# pm25-bme680.net
KiCad netlist of a schematic drawn in EAGLE
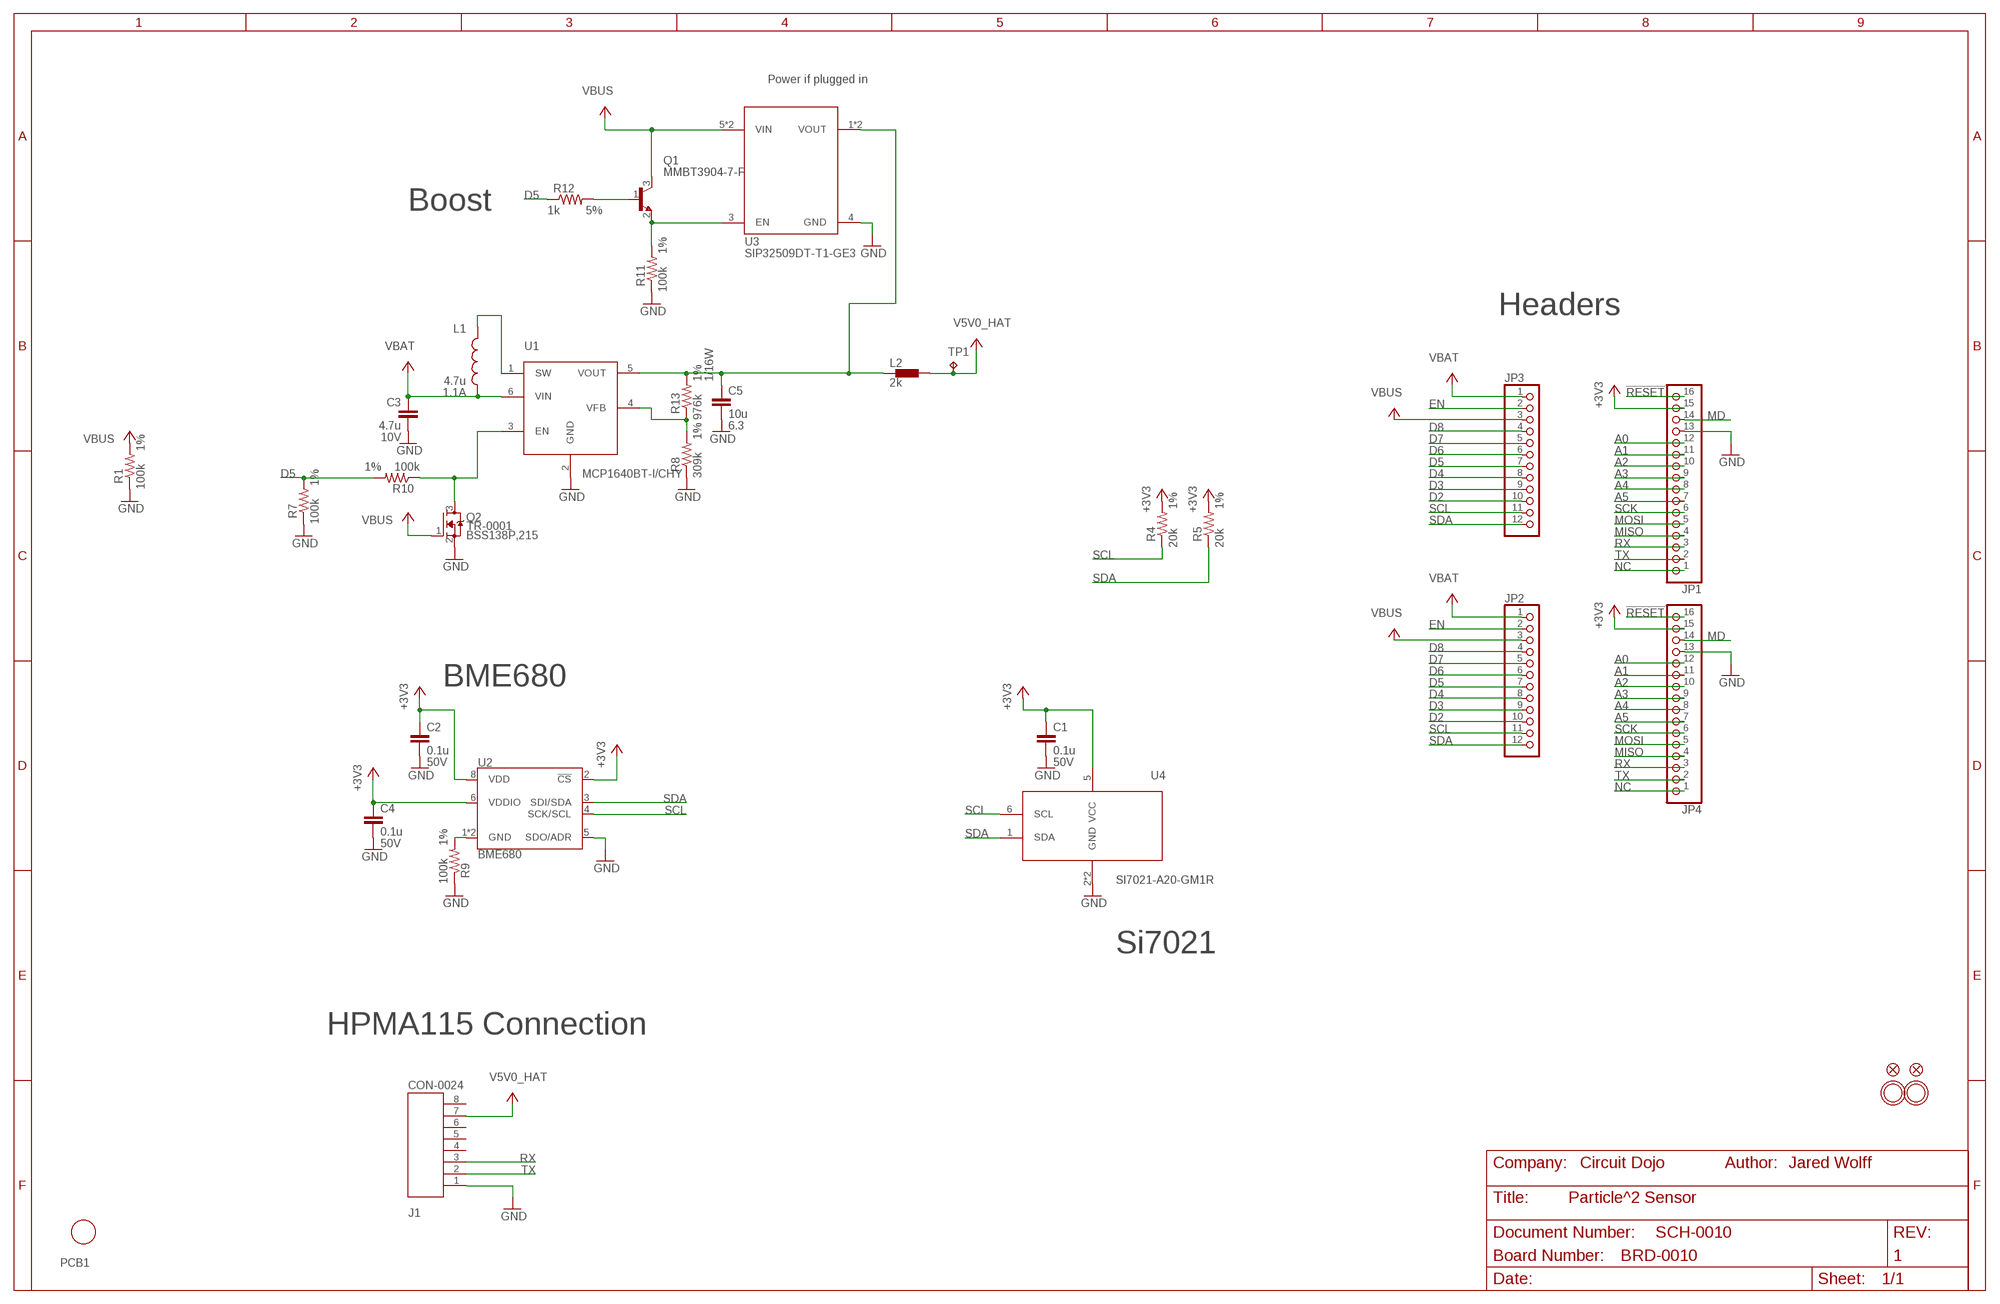
[diagram p0: schematic, sheet 1]

(export (version "E")
  (design (tool "Eeschema 10.0.6"))
  (components
    (comp (ref "C1")
      (value "0.1u")
      (footprint "eagle-import:CAPC1005X55N")
      (fields
        (field (name "VOLTHIGH") "50V")
        (field (name "MF") "Taiyo Yuden")
        (field (name "MPN") "UMK105BJ104KV-F")
      )
      (libsource (lib "eagle-import") (part "CAP-0017"))
    )
    (comp (ref "C2")
      (value "0.1u")
      (footprint "eagle-import:CAPC1005X55N")
      (fields
        (field (name "VOLTHIGH") "50V")
        (field (name "MF") "Taiyo Yuden")
        (field (name "MPN") "UMK105BJ104KV-F")
      )
      (libsource (lib "eagle-import") (part "CAP-0017"))
    )
    (comp (ref "C3")
      (value "4.7u")
      (footprint "eagle-import:C0603")
      (fields (field (name "VOLTHIGH") "10V") (field (name "MPN") "CL10A475MP5LNNC"))
      (libsource (lib "eagle-import") (part "CAP-0010"))
    )
    (comp (ref "C4")
      (value "0.1u")
      (footprint "eagle-import:CAPC1005X55N")
      (fields
        (field (name "VOLTHIGH") "50V")
        (field (name "MF") "Taiyo Yuden")
        (field (name "MPN") "UMK105BJ104KV-F")
      )
      (libsource (lib "eagle-import") (part "CAP-0017"))
    )
    (comp (ref "C5")
      (value "10u")
      (footprint "eagle-import:C0603")
      (fields (field (name "MPN") "JMK107ABJ106MA-T") (field (name "VOLTHIGH") "6.3"))
      (libsource (lib "eagle-import") (part "CAP-0603-10U-6.3V"))
    )
    (comp (ref "J1")
      (value "CON-0024")
      (footprint "eagle-import:0532610871")
      (fields (field (name "MPN") "0532610871"))
      (libsource (lib "eagle-import") (part "CON-0024"))
    )
    (comp (ref "JP1")
      (value "HEADER-1X16ROUND")
      (footprint "eagle-import:1X16_ROUND")
      (fields (field (name "MPN") "PPPC161LFBN-RC"))
      (libsource (lib "eagle-import") (part "HEADER-1X16ROUND"))
    )
    (comp (ref "JP2")
      (value "HEADER-1X12")
      (footprint "eagle-import:1X12_ROUND")
      (libsource (lib "eagle-import") (part "HEADER-1X12"))
    )
    (comp (ref "JP3")
      (value "HEADER-1X12")
      (footprint "eagle-import:1X12_ROUND")
      (fields (field (name "MPN") "PPPC121LFBN-RC"))
      (libsource (lib "eagle-import") (part "HEADER-1X12"))
    )
    (comp (ref "JP4")
      (value "HEADER-1X16ROUND")
      (footprint "eagle-import:1X16_ROUND")
      (libsource (lib "eagle-import") (part "HEADER-1X16ROUND"))
    )
    (comp (ref "L1")
      (value "4.7u")
      (footprint "eagle-import:IND-2P0X2P0X1P2")
      (fields (field (name "CURRENT") "1.1A") (field (name "MPN") "NRV2012T4R7MGF"))
      (libsource (lib "eagle-import") (part "IND-0003"))
    )
    (comp (ref "L2")
      (value "2k")
      (footprint "eagle-import:R0805")
      (fields (field (name "MPN") "CIM21J202NE"))
      (libsource (lib "eagle-import") (part "FERRITE-0805"))
    )
    (comp (ref "PCB1")
      (value "PCB-BME680-SI7021")
      (footprint "eagle-import:PLACEHOLDER")
      (fields (field (name "MPN") "BRD-0011"))
      (libsource (lib "eagle-import") (part "PCB-BME680-SI7021"))
    )
    (comp (ref "Q1")
      (value "TRANSISTOR-NPN-40V-0.2A-SOT23")
      (footprint "eagle-import:SOT23")
      (fields (field (name "MPN") "MMBT3904-7-F"))
      (libsource (lib "eagle-import") (part "TRANSISTOR-SOT23-NPN-40V-0.2A"))
    )
    (comp (ref "Q2")
      (value "TR-0001")
      (footprint "eagle-import:SOT23")
      (fields (field (name "MPN") "BSS138P,215"))
      (libsource (lib "eagle-import") (part "TR-0001"))
    )
    (comp (ref "R1")
      (value "100k")
      (footprint "eagle-import:R0402")
      (fields (field (name "TOLERANCE") "1%") (field (name "MPN") "RC0402FR07100KL"))
      (libsource (lib "eagle-import") (part "RES-0041"))
    )
    (comp (ref "R4")
      (value "20k")
      (footprint "eagle-import:R0402")
      (fields (field (name "TOLERANCE") "1%") (field (name "MPN") "RC0402FR-0720KL"))
      (libsource (lib "eagle-import") (part "RES-0054"))
    )
    (comp (ref "R5")
      (value "20k")
      (footprint "eagle-import:R0402")
      (fields (field (name "TOLERANCE") "1%") (field (name "MPN") "RC0402FR-0720KL"))
      (libsource (lib "eagle-import") (part "RES-0054"))
    )
    (comp (ref "R7")
      (value "100k")
      (footprint "eagle-import:R0402")
      (fields (field (name "TOLERANCE") "1%") (field (name "MPN") "RC0402FR07100KL"))
      (libsource (lib "eagle-import") (part "RES-0041"))
    )
    (comp (ref "R8")
      (value "309k")
      (footprint "eagle-import:R0402")
      (fields
        (field (name "MPN") "RC0402FR-07309KL")
        (field (name "POWER") "1/16W")
        (field (name "TOLERANCE") "1%")
      )
      (libsource (lib "eagle-import") (part "RES-0402-309K-1%"))
    )
    (comp (ref "R9")
      (value "100k")
      (footprint "eagle-import:R0402")
      (fields (field (name "TOLERANCE") "1%") (field (name "MPN") "RC0402FR07100KL"))
      (libsource (lib "eagle-import") (part "RES-0041"))
    )
    (comp (ref "R10")
      (value "100k")
      (footprint "eagle-import:R0402")
      (fields (field (name "TOLERANCE") "1%") (field (name "MPN") "RC0402FR07100KL"))
      (libsource (lib "eagle-import") (part "RES-0041"))
    )
    (comp (ref "R11")
      (value "100k")
      (footprint "eagle-import:R0402")
      (fields (field (name "TOLERANCE") "1%") (field (name "MPN") "RC0402FR07100KL"))
      (libsource (lib "eagle-import") (part "RES-0041"))
    )
    (comp (ref "R12")
      (value "1k")
      (footprint "eagle-import:R0402")
      (fields (field (name "TOLERANCE") "5%") (field (name "MPN") "RC0402JR-071KL"))
      (libsource (lib "eagle-import") (part "RES-0039"))
    )
    (comp (ref "R13")
      (value "976k")
      (footprint "eagle-import:R0402")
      (fields
        (field (name "MPN") "RC0402FR-07976KL")
        (field (name "POWER") "1/16W")
        (field (name "TOLERANCE") "1%")
      )
      (libsource (lib "eagle-import") (part "RES-0402-976K-1%"))
    )
    (comp (ref "TP1")
      (value "TP")
      (footprint "eagle-import:TP-1P27")
      (libsource (lib "eagle-import") (part "TP"))
    )
    (comp (ref "U$31")
      (value "MOUNTINGHOLE2.5")
      (footprint "eagle-import:MOUNTINGHOLE_2.5_PLATED")
      (libsource (lib "eagle-import") (part "MOUNTINGHOLE2.5"))
    )
    (comp (ref "U$32")
      (value "MOUNTINGHOLE2.5")
      (footprint "eagle-import:MOUNTINGHOLE_2.5_PLATED")
      (libsource (lib "eagle-import") (part "MOUNTINGHOLE2.5"))
    )
    (comp (ref "U$34")
      (value "FIDUCIAL\"\"")
      (footprint "eagle-import:FIDUCIAL_1MM")
      (libsource (lib "eagle-import") (part "FIDUCIAL{dblquote}{dblquote}"))
    )
    (comp (ref "U$35")
      (value "FIDUCIAL\"\"")
      (footprint "eagle-import:FIDUCIAL_1MM")
      (libsource (lib "eagle-import") (part "FIDUCIAL{dblquote}{dblquote}"))
    )
    (comp (ref "U1")
      (value "POWER-VREG-FB-EN-SW-350MA")
      (footprint "eagle-import:SOT23-6")
      (fields (field (name "MPN") "MCP1640BT-I/CHY"))
      (libsource (lib "eagle-import") (part "POWER-VREG-FB-EN-SW-350MA"))
    )
    (comp (ref "U2")
      (value "BME680")
      (footprint "eagle-import:LGA3.0X3.0")
      (fields (field (name "MF") "Bosch Sensortec"))
      (libsource (lib "eagle-import") (part "BME680"))
    )
    (comp (ref "U3")
      (value "POWER-SWITCH-SIP32509DT")
      (footprint "eagle-import:SOT23-6")
      (fields (field (name "MPN") "SIP32509DT-T1-GE3"))
      (libsource (lib "eagle-import") (part "POWER-SWITCH-SIP32509DT"))
    )
    (comp (ref "U4")
      (value "SI7021-A20-GM1R")
      (footprint "eagle-import:SON100P300X300X80-7N")
      (fields (field (name "MPN") "SI7021-A20-GM1R"))
      (libsource (lib "eagle-import") (part "SI7021-A20-GM1R"))
    )
  )
  (nets
    (net (code "1") (name "+3V3") (class "Default")
      (node (ref "C1") (pin "1") (pinfunction "1_1") (pintype "passive"))
      (node (ref "C2") (pin "1") (pinfunction "1_1") (pintype "passive"))
      (node (ref "C4") (pin "1") (pinfunction "1_1") (pintype "passive"))
      (node (ref "JP1") (pin "15") (pinfunction "15_15") (pintype "passive"))
      (node (ref "JP4") (pin "15") (pinfunction "15_15") (pintype "passive"))
      (node (ref "R4") (pin "2") (pinfunction "2_2") (pintype "passive"))
      (node (ref "R5") (pin "2") (pinfunction "2_2") (pintype "passive"))
      (node (ref "U2") (pin "2") (pinfunction "~{CS}_2") (pintype "bidirectional"))
      (node (ref "U2") (pin "6") (pinfunction "VDDIO_6") (pintype "bidirectional"))
      (node (ref "U2") (pin "8") (pinfunction "VDD_8") (pintype "bidirectional"))
      (node (ref "U4") (pin "5") (pinfunction "VCC_5") (pintype "bidirectional"))
    )
    (net (code "2") (name "/A0") (class "Default")
      (node (ref "JP1") (pin "12") (pinfunction "12_12") (pintype "passive"))
      (node (ref "JP4") (pin "12") (pinfunction "12_12") (pintype "passive"))
    )
    (net (code "3") (name "/A1") (class "Default")
      (node (ref "JP1") (pin "11") (pinfunction "11_11") (pintype "passive"))
      (node (ref "JP4") (pin "11") (pinfunction "11_11") (pintype "passive"))
    )
    (net (code "4") (name "/A2") (class "Default")
      (node (ref "JP1") (pin "10") (pinfunction "10_10") (pintype "passive"))
      (node (ref "JP4") (pin "10") (pinfunction "10_10") (pintype "passive"))
    )
    (net (code "5") (name "/A3") (class "Default")
      (node (ref "JP1") (pin "9") (pinfunction "9_9") (pintype "passive"))
      (node (ref "JP4") (pin "9") (pinfunction "9_9") (pintype "passive"))
    )
    (net (code "6") (name "/A4") (class "Default")
      (node (ref "JP1") (pin "8") (pinfunction "8_8") (pintype "passive"))
      (node (ref "JP4") (pin "8") (pinfunction "8_8") (pintype "passive"))
    )
    (net (code "7") (name "/A5") (class "Default")
      (node (ref "JP1") (pin "7") (pinfunction "7_7") (pintype "passive"))
      (node (ref "JP4") (pin "7") (pinfunction "7_7") (pintype "passive"))
    )
    (net (code "8") (name "/D2") (class "Default")
      (node (ref "JP2") (pin "10") (pinfunction "10_10") (pintype "passive"))
      (node (ref "JP3") (pin "10") (pinfunction "10_10") (pintype "passive"))
    )
    (net (code "9") (name "/D3") (class "Default")
      (node (ref "JP2") (pin "9") (pinfunction "9_9") (pintype "passive"))
      (node (ref "JP3") (pin "9") (pinfunction "9_9") (pintype "passive"))
    )
    (net (code "10") (name "/D4") (class "Default")
      (node (ref "JP2") (pin "8") (pinfunction "8_8") (pintype "passive"))
      (node (ref "JP3") (pin "8") (pinfunction "8_8") (pintype "passive"))
    )
    (net (code "11") (name "/D5") (class "Default")
      (node (ref "JP2") (pin "7") (pinfunction "7_7") (pintype "passive"))
      (node (ref "JP3") (pin "7") (pinfunction "7_7") (pintype "passive"))
      (node (ref "R10") (pin "2") (pinfunction "2_2") (pintype "passive"))
      (node (ref "R12") (pin "1") (pinfunction "1_1") (pintype "passive"))
      (node (ref "R7") (pin "2") (pinfunction "2_2") (pintype "passive"))
    )
    (net (code "12") (name "/D6") (class "Default")
      (node (ref "JP2") (pin "6") (pinfunction "6_6") (pintype "passive"))
      (node (ref "JP3") (pin "6") (pinfunction "6_6") (pintype "passive"))
    )
    (net (code "13") (name "/D7") (class "Default")
      (node (ref "JP2") (pin "5") (pinfunction "5_5") (pintype "passive"))
      (node (ref "JP3") (pin "5") (pinfunction "5_5") (pintype "passive"))
    )
    (net (code "14") (name "/D8") (class "Default")
      (node (ref "JP2") (pin "4") (pinfunction "4_4") (pintype "passive"))
      (node (ref "JP3") (pin "4") (pinfunction "4_4") (pintype "passive"))
    )
    (net (code "15") (name "/EN") (class "Default")
      (node (ref "JP2") (pin "2") (pinfunction "2_2") (pintype "passive"))
      (node (ref "JP3") (pin "2") (pinfunction "2_2") (pintype "passive"))
    )
    (net (code "16") (name "/MD") (class "Default")
      (node (ref "JP1") (pin "14") (pinfunction "14_14") (pintype "passive"))
      (node (ref "JP4") (pin "14") (pinfunction "14_14") (pintype "passive"))
    )
    (net (code "17") (name "/MISO") (class "Default")
      (node (ref "JP1") (pin "4") (pinfunction "4_4") (pintype "passive"))
      (node (ref "JP4") (pin "4") (pinfunction "4_4") (pintype "passive"))
    )
    (net (code "18") (name "/MOSI") (class "Default")
      (node (ref "JP1") (pin "5") (pinfunction "5_5") (pintype "passive"))
      (node (ref "JP4") (pin "5") (pinfunction "5_5") (pintype "passive"))
    )
    (net (code "19") (name "/NC") (class "Default")
      (node (ref "JP1") (pin "1") (pinfunction "1_1") (pintype "passive"))
      (node (ref "JP4") (pin "1") (pinfunction "1_1") (pintype "passive"))
    )
    (net (code "20") (name "/RX") (class "Default")
      (node (ref "J1") (pin "3") (pinfunction "P$3_3") (pintype "bidirectional"))
      (node (ref "JP1") (pin "3") (pinfunction "3_3") (pintype "passive"))
      (node (ref "JP4") (pin "3") (pinfunction "3_3") (pintype "passive"))
    )
    (net (code "21") (name "/SCK") (class "Default")
      (node (ref "JP1") (pin "6") (pinfunction "6_6") (pintype "passive"))
      (node (ref "JP4") (pin "6") (pinfunction "6_6") (pintype "passive"))
    )
    (net (code "22") (name "/SCL") (class "Default")
      (node (ref "JP2") (pin "11") (pinfunction "11_11") (pintype "passive"))
      (node (ref "JP3") (pin "11") (pinfunction "11_11") (pintype "passive"))
      (node (ref "R4") (pin "1") (pinfunction "1_1") (pintype "passive"))
      (node (ref "U2") (pin "4") (pinfunction "SCK/SCL_4") (pintype "bidirectional"))
      (node (ref "U4") (pin "6") (pinfunction "SCL_6") (pintype "bidirectional"))
    )
    (net (code "23") (name "/SDA") (class "Default")
      (node (ref "JP2") (pin "12") (pinfunction "12_12") (pintype "passive"))
      (node (ref "JP3") (pin "12") (pinfunction "12_12") (pintype "passive"))
      (node (ref "R5") (pin "1") (pinfunction "1_1") (pintype "passive"))
      (node (ref "U2") (pin "3") (pinfunction "SDI/SDA_3") (pintype "bidirectional"))
      (node (ref "U4") (pin "1") (pinfunction "SDA_1") (pintype "bidirectional"))
    )
    (net (code "24") (name "/TX") (class "Default")
      (node (ref "J1") (pin "2") (pinfunction "P$2_2") (pintype "bidirectional"))
      (node (ref "JP1") (pin "2") (pinfunction "2_2") (pintype "passive"))
      (node (ref "JP4") (pin "2") (pinfunction "2_2") (pintype "passive"))
    )
    (net (code "25") (name "/~{RESET}") (class "Default")
      (node (ref "JP1") (pin "16") (pinfunction "16_16") (pintype "passive"))
      (node (ref "JP4") (pin "16") (pinfunction "16_16") (pintype "passive"))
    )
    (net (code "26") (name "GND") (class "Default")
      (node (ref "C1") (pin "2") (pinfunction "2_2") (pintype "passive"))
      (node (ref "C2") (pin "2") (pinfunction "2_2") (pintype "passive"))
      (node (ref "C3") (pin "2") (pinfunction "2_2") (pintype "passive"))
      (node (ref "C4") (pin "2") (pinfunction "2_2") (pintype "passive"))
      (node (ref "C5") (pin "2") (pinfunction "2_2") (pintype "passive"))
      (node (ref "J1") (pin "1") (pinfunction "P$1_1") (pintype "bidirectional"))
      (node (ref "JP1") (pin "13") (pinfunction "13_13") (pintype "passive"))
      (node (ref "JP4") (pin "13") (pinfunction "13_13") (pintype "passive"))
      (node (ref "Q2") (pin "2") (pinfunction "S_2") (pintype "bidirectional"))
      (node (ref "R1") (pin "1") (pinfunction "1_1") (pintype "passive"))
      (node (ref "R11") (pin "1") (pinfunction "1_1") (pintype "passive"))
      (node (ref "R7") (pin "1") (pinfunction "1_1") (pintype "passive"))
      (node (ref "R8") (pin "1") (pinfunction "1_1") (pintype "passive"))
      (node (ref "R9") (pin "1") (pinfunction "1_1") (pintype "passive"))
      (node (ref "U1") (pin "2") (pinfunction "GND_2") (pintype "bidirectional"))
      (node (ref "U2") (pin "5") (pinfunction "SDO/ADR_5") (pintype "bidirectional"))
      (node (ref "U3") (pin "4") (pinfunction "GND_4") (pintype "power_in"))
      (node (ref "U4") (pin "2") (pinfunction "GND_2") (pintype "bidirectional"))
      (node (ref "U4") (pin "7") (pinfunction "GND_7") (pintype "bidirectional"))
    )
    (net (code "27") (name "Net-(L1-1)") (class "Default")
      (node (ref "L1") (pin "P$1") (pinfunction "1_P$1") (pintype "passive"))
      (node (ref "U1") (pin "1") (pinfunction "SW_1") (pintype "bidirectional"))
    )
    (net (code "28") (name "Net-(Q1-B)") (class "Default")
      (node (ref "Q1") (pin "1") (pinfunction "B_1") (pintype "passive"))
      (node (ref "R12") (pin "2") (pinfunction "2_2") (pintype "passive"))
    )
    (net (code "29") (name "Net-(Q1-E)") (class "Default")
      (node (ref "Q1") (pin "2") (pinfunction "E_2") (pintype "passive"))
      (node (ref "R11") (pin "2") (pinfunction "2_2") (pintype "passive"))
      (node (ref "U3") (pin "3") (pinfunction "EN_3") (pintype "input"))
    )
    (net (code "30") (name "Net-(Q2-D)") (class "Default")
      (node (ref "Q2") (pin "3") (pinfunction "D_3") (pintype "bidirectional"))
      (node (ref "R10") (pin "1") (pinfunction "1_1") (pintype "passive"))
      (node (ref "U1") (pin "3") (pinfunction "EN_3") (pintype "bidirectional"))
    )
    (net (code "31") (name "Net-(R9-Pad2)") (class "Default")
      (node (ref "R9") (pin "2") (pinfunction "2_2") (pintype "passive"))
      (node (ref "U2") (pin "1") (pinfunction "GND_1") (pintype "bidirectional"))
      (node (ref "U2") (pin "7") (pinfunction "GND_7") (pintype "bidirectional"))
    )
    (net (code "32") (name "Net-(U1-VFB)") (class "Default")
      (node (ref "R13") (pin "1") (pinfunction "1_1") (pintype "passive"))
      (node (ref "R8") (pin "2") (pinfunction "2_2") (pintype "passive"))
      (node (ref "U1") (pin "4") (pinfunction "VFB_4") (pintype "bidirectional"))
    )
    (net (code "33") (name "Net-(U1-VOUT)") (class "Default")
      (node (ref "C5") (pin "1") (pinfunction "1_1") (pintype "passive"))
      (node (ref "L2") (pin "1") (pinfunction "1_1") (pintype "passive"))
      (node (ref "R13") (pin "2") (pinfunction "2_2") (pintype "passive"))
      (node (ref "U1") (pin "5") (pinfunction "VOUT_5") (pintype "bidirectional"))
      (node (ref "U3") (pin "1") (pinfunction "VOUT_1") (pintype "power_in"))
      (node (ref "U3") (pin "2") (pinfunction "VOUT_2") (pintype "power_in"))
    )
    (net (code "34") (name "V5V0_HAT") (class "Default")
      (node (ref "J1") (pin "7") (pinfunction "P$7_7") (pintype "bidirectional"))
      (node (ref "L2") (pin "2") (pinfunction "2_2") (pintype "passive"))
      (node (ref "TP1") (pin "P$1") (pinfunction "TP_P$1") (pintype "input"))
      (node (ref "TP1") (pin "P$2") (pinfunction "TP_P$2") (pintype "input"))
      (node (ref "TP1") (pin "TP") (pinfunction "TP_TP") (pintype "input"))
    )
    (net (code "35") (name "VBAT") (class "Default")
      (node (ref "C3") (pin "1") (pinfunction "1_1") (pintype "passive"))
      (node (ref "JP2") (pin "1") (pinfunction "1_1") (pintype "passive"))
      (node (ref "JP3") (pin "1") (pinfunction "1_1") (pintype "passive"))
      (node (ref "L1") (pin "P$2") (pinfunction "2_P$2") (pintype "passive"))
      (node (ref "U1") (pin "6") (pinfunction "VIN_6") (pintype "bidirectional"))
    )
    (net (code "36") (name "VBUS") (class "Default")
      (node (ref "JP2") (pin "3") (pinfunction "3_3") (pintype "passive"))
      (node (ref "JP3") (pin "3") (pinfunction "3_3") (pintype "passive"))
      (node (ref "Q1") (pin "3") (pinfunction "C_3") (pintype "passive"))
      (node (ref "Q2") (pin "1") (pinfunction "G_1") (pintype "bidirectional"))
      (node (ref "R1") (pin "2") (pinfunction "2_2") (pintype "passive"))
      (node (ref "U3") (pin "5") (pinfunction "VIN_5") (pintype "power_in"))
      (node (ref "U3") (pin "6") (pinfunction "VIN_6") (pintype "power_in"))
    )
    (net (code "37") (name "unconnected-(J1-P$4-Pad4)") (class "Default")
      (node (ref "J1") (pin "4") (pinfunction "P$4_4") (pintype "bidirectional"))
    )
    (net (code "38") (name "unconnected-(J1-P$5-Pad5)") (class "Default")
      (node (ref "J1") (pin "5") (pinfunction "P$5_5") (pintype "bidirectional"))
    )
    (net (code "39") (name "unconnected-(J1-P$6-Pad6)") (class "Default")
      (node (ref "J1") (pin "6") (pinfunction "P$6_6") (pintype "bidirectional"))
    )
    (net (code "40") (name "unconnected-(J1-P$8-Pad8)") (class "Default")
      (node (ref "J1") (pin "8") (pinfunction "P$8_8") (pintype "bidirectional"))
    )
  )
)
